# STlink_V3E_PWR.net
KiCad netlist of a schematic drawn in Altium Designer
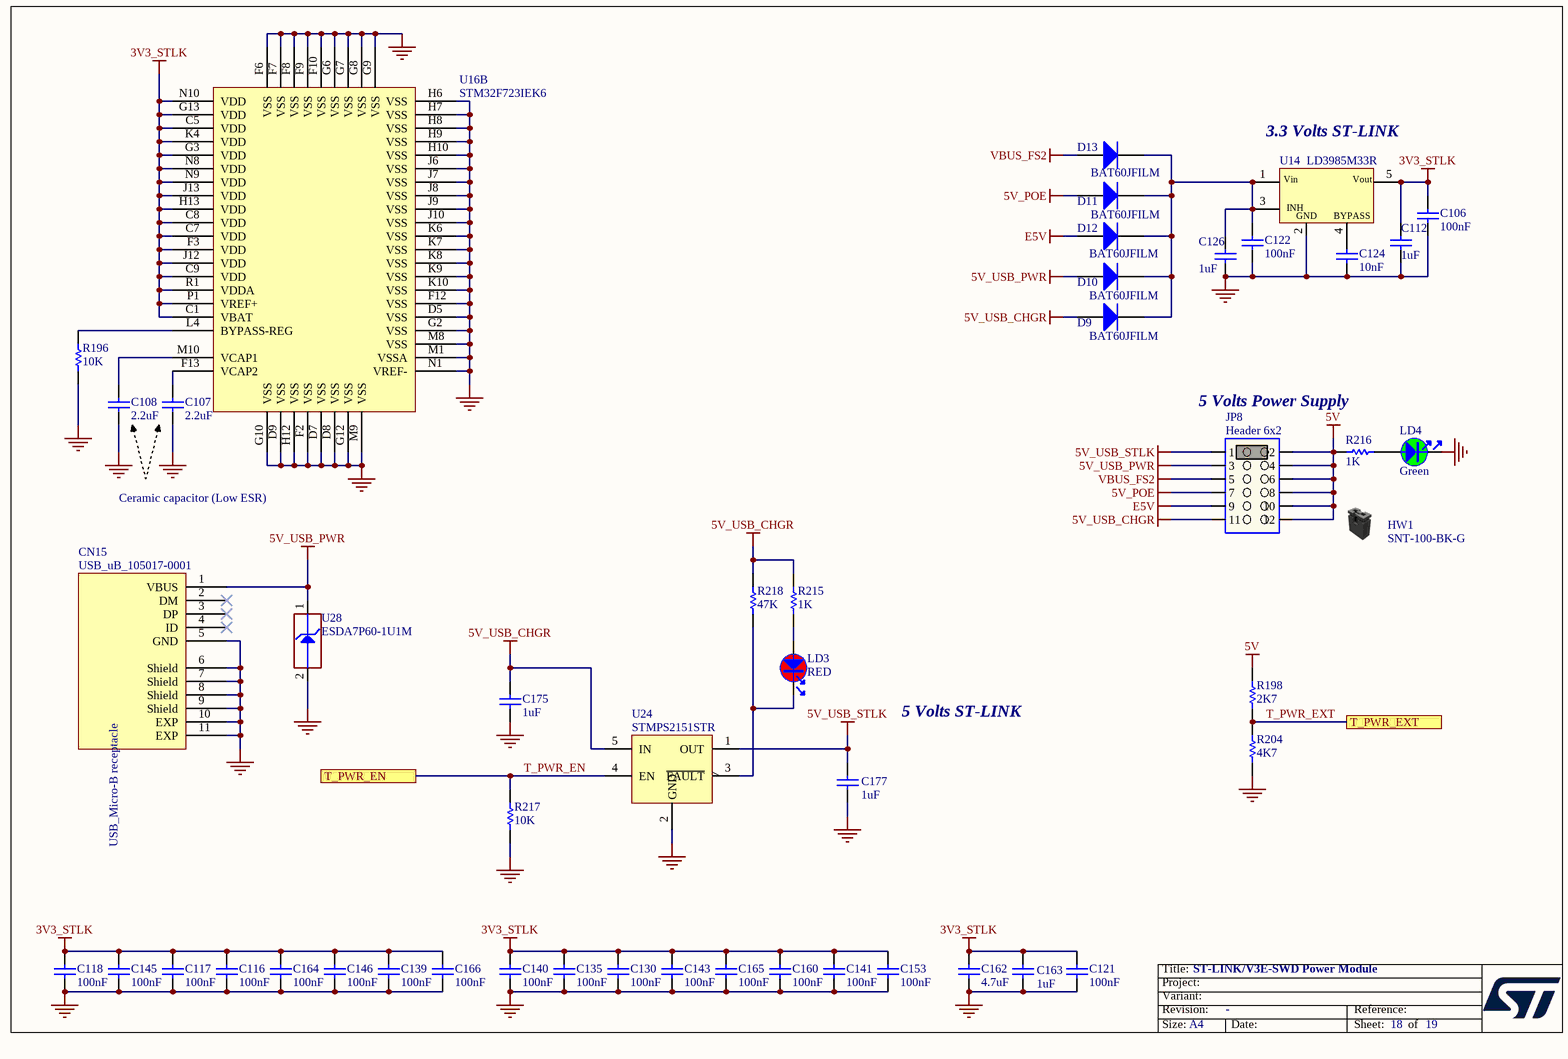
[diagram p0: STlink_V3E_PWR.SchDoc]

(export (version "E")
  (design (tool "Eeschema 10.0.6"))
  (components
    (comp (ref "C106")
      (value "100nF")
      (footprint "C0402")
      (description "Capacitor, MLCC, 100nF, 16V, X7R, +/-10%, 0402, T=0.5mm")
      (fields
        (field (name "INTERNAL_PART_NUMBER") "MCD-00006")
        (field (name "MANUFACTURER_PART_NUMBER") "CC0402KRX7R7BB104")
      )
      (libsource (lib "MCD_PARTS_database") (part "Capacitor"))
    )
    (comp (ref "C107")
      (value "2.2uF")
      (footprint "C1206_H1P15")
      (description "Capacitor, MLCC, 2.2uF, 16V, X7R, 10%, 1206, T=1,15mm")
      (fields
        (field (name "INTERNAL_PART_NUMBER") "MCD-00008")
        (field (name "MANUFACTURER_PART_NUMBER") "CC1206KKX7R7BB225")
        (field (name "PROVIDED_BY") "Subcon")
      )
      (libsource (lib "MCD_PARTS_database") (part "Capacitor"))
    )
    (comp (ref "C108")
      (value "2.2uF")
      (footprint "C1206_H1P15")
      (description "Capacitor, MLCC, 2.2uF, 16V, X7R, 10%, 1206, T=1,15mm")
      (fields
        (field (name "INTERNAL_PART_NUMBER") "MCD-00008")
        (field (name "MANUFACTURER_PART_NUMBER") "CC1206KKX7R7BB225")
        (field (name "PROVIDED_BY") "Subcon")
      )
      (libsource (lib "MCD_PARTS_database") (part "Capacitor"))
    )
    (comp (ref "C112")
      (value "1uF")
      (footprint "C0603")
      (description "Capacitor, MLCC, 1uF, 16V, X5R, 10%, 0603, T=0,8mm")
      (fields
        (field (name "INTERNAL_PART_NUMBER") "MCD-00010")
        (field (name "MANUFACTURER_PART_NUMBER") "CC0603KRX5R7BB105")
        (field (name "PROVIDED_BY") "Subcon")
      )
      (libsource (lib "MCD_PARTS_database") (part "Capacitor"))
    )
    (comp (ref "C116")
      (value "100nF")
      (footprint "C0402")
      (description "Capacitor, MLCC, 100nF, 16V, X7R, +/-10%, 0402, T=0.5mm")
      (fields
        (field (name "INTERNAL_PART_NUMBER") "MCD-00006")
        (field (name "MANUFACTURER_PART_NUMBER") "CC0402KRX7R7BB104")
      )
      (libsource (lib "MCD_PARTS_database") (part "Capacitor"))
    )
    (comp (ref "C117")
      (value "100nF")
      (footprint "C0402")
      (description "Capacitor, MLCC, 100nF, 16V, X7R, +/-10%, 0402, T=0.5mm")
      (fields
        (field (name "INTERNAL_PART_NUMBER") "MCD-00006")
        (field (name "MANUFACTURER_PART_NUMBER") "CC0402KRX7R7BB104")
      )
      (libsource (lib "MCD_PARTS_database") (part "Capacitor"))
    )
    (comp (ref "C118")
      (value "100nF")
      (footprint "C0402")
      (description "Capacitor, MLCC, 100nF, 16V, X7R, +/-10%, 0402, T=0.5mm")
      (fields
        (field (name "INTERNAL_PART_NUMBER") "MCD-00006")
        (field (name "MANUFACTURER_PART_NUMBER") "CC0402KRX7R7BB104")
      )
      (libsource (lib "MCD_PARTS_database") (part "Capacitor"))
    )
    (comp (ref "C121")
      (value "100nF")
      (footprint "C0402")
      (description "Capacitor, MLCC, 100nF, 16V, X7R, +/-10%, 0402, T=0.5mm")
      (fields
        (field (name "INTERNAL_PART_NUMBER") "MCD-00006")
        (field (name "MANUFACTURER_PART_NUMBER") "CC0402KRX7R7BB104")
      )
      (libsource (lib "MCD_PARTS_database") (part "Capacitor"))
    )
    (comp (ref "C122")
      (value "100nF")
      (footprint "C0402")
      (description "Capacitor, MLCC, 100nF, 16V, X7R, +/-10%, 0402, T=0.5mm")
      (fields
        (field (name "INTERNAL_PART_NUMBER") "MCD-00006")
        (field (name "MANUFACTURER_PART_NUMBER") "CC0402KRX7R7BB104")
      )
      (libsource (lib "MCD_PARTS_database") (part "Capacitor"))
    )
    (comp (ref "C124")
      (value "10nF")
      (footprint "C0402")
      (description "Capacitor, MLCC, 10nF, 16V, X7R, 10%, 0402, T=0.5mm")
      (fields
        (field (name "INTERNAL_PART_NUMBER") "MCD-00011")
        (field (name "MANUFACTURER_PART_NUMBER") "CC0402KRX7R7BB103")
        (field (name "PROVIDED_BY") "Subcon")
      )
      (libsource (lib "MCD_PARTS_database") (part "Capacitor"))
    )
    (comp (ref "C126")
      (value "1uF")
      (footprint "C0603")
      (description "Capacitor, MLCC, 1uF, 6V3, X5R, 10%, 0603, T=0,8mm")
      (fields
        (field (name "INTERNAL_PART_NUMBER") "MCD-00238")
        (field (name "MANUFACTURER_PART_NUMBER") "CC0603KRX5R5BB105")
        (field (name "PROVIDED_BY") "Subcon")
      )
      (libsource (lib "MCD_PARTS_database") (part "Capacitor"))
    )
    (comp (ref "C130")
      (value "100nF")
      (footprint "C0402")
      (description "Capacitor, MLCC, 100nF, 16V, X7R, +/-10%, 0402, T=0.5mm")
      (fields
        (field (name "INTERNAL_PART_NUMBER") "MCD-00006")
        (field (name "MANUFACTURER_PART_NUMBER") "CC0402KRX7R7BB104")
      )
      (libsource (lib "MCD_PARTS_database") (part "Capacitor"))
    )
    (comp (ref "C135")
      (value "100nF")
      (footprint "C0402")
      (description "Capacitor, MLCC, 100nF, 16V, X7R, +/-10%, 0402, T=0.5mm")
      (fields
        (field (name "INTERNAL_PART_NUMBER") "MCD-00006")
        (field (name "MANUFACTURER_PART_NUMBER") "CC0402KRX7R7BB104")
      )
      (libsource (lib "MCD_PARTS_database") (part "Capacitor"))
    )
    (comp (ref "C139")
      (value "100nF")
      (footprint "C0402")
      (description "Capacitor, MLCC, 100nF, 16V, X7R, +/-10%, 0402, T=0.5mm")
      (fields
        (field (name "INTERNAL_PART_NUMBER") "MCD-00006")
        (field (name "MANUFACTURER_PART_NUMBER") "CC0402KRX7R7BB104")
      )
      (libsource (lib "MCD_PARTS_database") (part "Capacitor"))
    )
    (comp (ref "C140")
      (value "100nF")
      (footprint "C0402")
      (description "Capacitor, MLCC, 100nF, 16V, X7R, +/-10%, 0402, T=0.5mm")
      (fields
        (field (name "INTERNAL_PART_NUMBER") "MCD-00006")
        (field (name "MANUFACTURER_PART_NUMBER") "CC0402KRX7R7BB104")
      )
      (libsource (lib "MCD_PARTS_database") (part "Capacitor"))
    )
    (comp (ref "C141")
      (value "100nF")
      (footprint "C0402")
      (description "Capacitor, MLCC, 100nF, 16V, X7R, +/-10%, 0402, T=0.5mm")
      (fields
        (field (name "INTERNAL_PART_NUMBER") "MCD-00006")
        (field (name "MANUFACTURER_PART_NUMBER") "CC0402KRX7R7BB104")
      )
      (libsource (lib "MCD_PARTS_database") (part "Capacitor"))
    )
    (comp (ref "C143")
      (value "100nF")
      (footprint "C0402")
      (description "Capacitor, MLCC, 100nF, 16V, X7R, +/-10%, 0402, T=0.5mm")
      (fields
        (field (name "INTERNAL_PART_NUMBER") "MCD-00006")
        (field (name "MANUFACTURER_PART_NUMBER") "CC0402KRX7R7BB104")
      )
      (libsource (lib "MCD_PARTS_database") (part "Capacitor"))
    )
    (comp (ref "C145")
      (value "100nF")
      (footprint "C0402")
      (description "Capacitor, MLCC, 100nF, 16V, X7R, +/-10%, 0402, T=0.5mm")
      (fields
        (field (name "INTERNAL_PART_NUMBER") "MCD-00006")
        (field (name "MANUFACTURER_PART_NUMBER") "CC0402KRX7R7BB104")
      )
      (libsource (lib "MCD_PARTS_database") (part "Capacitor"))
    )
    (comp (ref "C146")
      (value "100nF")
      (footprint "C0402")
      (description "Capacitor, MLCC, 100nF, 16V, X7R, +/-10%, 0402, T=0.5mm")
      (fields
        (field (name "INTERNAL_PART_NUMBER") "MCD-00006")
        (field (name "MANUFACTURER_PART_NUMBER") "CC0402KRX7R7BB104")
      )
      (libsource (lib "MCD_PARTS_database") (part "Capacitor"))
    )
    (comp (ref "C153")
      (value "100nF")
      (footprint "C0402")
      (description "Capacitor, MLCC, 100nF, 16V, X7R, +/-10%, 0402, T=0.5mm")
      (fields
        (field (name "INTERNAL_PART_NUMBER") "MCD-00006")
        (field (name "MANUFACTURER_PART_NUMBER") "CC0402KRX7R7BB104")
      )
      (libsource (lib "MCD_PARTS_database") (part "Capacitor"))
    )
    (comp (ref "C160")
      (value "100nF")
      (footprint "C0402")
      (description "Capacitor, MLCC, 100nF, 16V, X7R, +/-10%, 0402, T=0.5mm")
      (fields
        (field (name "INTERNAL_PART_NUMBER") "MCD-00006")
        (field (name "MANUFACTURER_PART_NUMBER") "CC0402KRX7R7BB104")
      )
      (libsource (lib "MCD_PARTS_database") (part "Capacitor"))
    )
    (comp (ref "C162")
      (value "4.7uF")
      (footprint "C0603")
      (description "Capacitor, MLCC, 4.7uF, 16V, X5R, 10%, 0603, T=0.8mm")
      (fields
        (field (name "INTERNAL_PART_NUMBER") "MCD-00009")
        (field (name "MANUFACTURER_PART_NUMBER") "CC0603KRX5R7BB475")
        (field (name "PROVIDED_BY") "subcon")
      )
      (libsource (lib "MCD_PARTS_database") (part "Capacitor"))
    )
    (comp (ref "C163")
      (value "1uF")
      (footprint "C0603")
      (description "Capacitor, MLCC, 1uF, 16V, X5R, 10%, 0603, T=0,8mm")
      (fields
        (field (name "INTERNAL_PART_NUMBER") "MCD-00010")
        (field (name "MANUFACTURER_PART_NUMBER") "CC0603KRX5R7BB105")
        (field (name "PROVIDED_BY") "Subcon")
      )
      (libsource (lib "MCD_PARTS_database") (part "Capacitor"))
    )
    (comp (ref "C164")
      (value "100nF")
      (footprint "C0402")
      (description "Capacitor, MLCC, 100nF, 16V, X7R, +/-10%, 0402, T=0.5mm")
      (fields
        (field (name "INTERNAL_PART_NUMBER") "MCD-00006")
        (field (name "MANUFACTURER_PART_NUMBER") "CC0402KRX7R7BB104")
      )
      (libsource (lib "MCD_PARTS_database") (part "Capacitor"))
    )
    (comp (ref "C165")
      (value "100nF")
      (footprint "C0402")
      (description "Capacitor, MLCC, 100nF, 16V, X7R, +/-10%, 0402, T=0.5mm")
      (fields
        (field (name "INTERNAL_PART_NUMBER") "MCD-00006")
        (field (name "MANUFACTURER_PART_NUMBER") "CC0402KRX7R7BB104")
      )
      (libsource (lib "MCD_PARTS_database") (part "Capacitor"))
    )
    (comp (ref "C166")
      (value "100nF")
      (footprint "C0402")
      (description "Capacitor, MLCC, 100nF, 16V, X7R, +/-10%, 0402, T=0.5mm")
      (fields
        (field (name "INTERNAL_PART_NUMBER") "MCD-00006")
        (field (name "MANUFACTURER_PART_NUMBER") "CC0402KRX7R7BB104")
      )
      (libsource (lib "MCD_PARTS_database") (part "Capacitor"))
    )
    (comp (ref "C175")
      (value "1uF")
      (footprint "C0603")
      (description "Capacitor, MLCC, 1uF, 16V, X5R, 10%, 0603, T=0,8mm")
      (fields
        (field (name "INTERNAL_PART_NUMBER") "MCD-00010")
        (field (name "MANUFACTURER_PART_NUMBER") "CC0603KRX5R7BB105")
        (field (name "PROVIDED_BY") "Subcon")
      )
      (libsource (lib "MCD_PARTS_database") (part "Capacitor"))
    )
    (comp (ref "C177")
      (value "1uF")
      (footprint "C0603")
      (description "Capacitor, MLCC, 1uF, 16V, X5R, 10%, 0603, T=0,8mm")
      (fields
        (field (name "INTERNAL_PART_NUMBER") "MCD-00010")
        (field (name "MANUFACTURER_PART_NUMBER") "CC0603KRX5R7BB105")
        (field (name "PROVIDED_BY") "Subcon")
      )
      (libsource (lib "MCD_PARTS_database") (part "Capacitor"))
    )
    (comp (ref "CN15")
      (value "USB_uB_105017-0001")
      (footprint "CON_USBMICROB_MOLEX_105017-0001_H2P90")
      (description "USB-MICRO-B, 0.65mm, RA, SMT, Bottom Mount,")
      (fields
        (field (name "INTERNAL_PART_NUMBER") "MCD-00028")
        (field (name "MANUFACTURER_PART_NUMBER") "1050170001")
        (field (name "PROVIDED_BY") "Subcon")
      )
      (libsource (lib "MCD_PARTS_database") (part "USB_uB_105017.0001"))
    )
    (comp (ref "D9")
      (value "BAT60JFILM")
      (footprint "DIO_SOD323")
      (fields
        (field (name "INTERNAL_PART_NUMBER") "MCD-00034")
        (field (name "MANUFACTURER") "STMICROELECTRONICS")
        (field (name "BMS_PART_NUMBER") "9151097")
        (field (name "PROVIDED_BY") "Subcon")
      )
      (libsource (lib "MCD_PARTS_database") (part "BAT60JFILM"))
    )
    (comp (ref "D10")
      (value "BAT60JFILM")
      (footprint "DIO_SOD323")
      (fields
        (field (name "INTERNAL_PART_NUMBER") "MCD-00034")
        (field (name "MANUFACTURER") "STMICROELECTRONICS")
        (field (name "BMS_PART_NUMBER") "9151097")
        (field (name "PROVIDED_BY") "Subcon")
      )
      (libsource (lib "MCD_PARTS_database") (part "BAT60JFILM"))
    )
    (comp (ref "D11")
      (value "BAT60JFILM")
      (footprint "DIO_SOD323")
      (fields
        (field (name "INTERNAL_PART_NUMBER") "MCD-00034")
        (field (name "MANUFACTURER") "STMICROELECTRONICS")
        (field (name "BMS_PART_NUMBER") "9151097")
        (field (name "PROVIDED_BY") "Subcon")
      )
      (libsource (lib "MCD_PARTS_database") (part "BAT60JFILM"))
    )
    (comp (ref "D12")
      (value "BAT60JFILM")
      (footprint "DIO_SOD323")
      (fields
        (field (name "INTERNAL_PART_NUMBER") "MCD-00034")
        (field (name "MANUFACTURER") "STMICROELECTRONICS")
        (field (name "BMS_PART_NUMBER") "9151097")
        (field (name "PROVIDED_BY") "Subcon")
      )
      (libsource (lib "MCD_PARTS_database") (part "BAT60JFILM"))
    )
    (comp (ref "D13")
      (value "BAT60JFILM")
      (footprint "DIO_SOD323")
      (fields
        (field (name "INTERNAL_PART_NUMBER") "MCD-00034")
        (field (name "MANUFACTURER") "STMICROELECTRONICS")
        (field (name "BMS_PART_NUMBER") "9151097")
        (field (name "PROVIDED_BY") "Subcon")
      )
      (libsource (lib "MCD_PARTS_database") (part "BAT60JFILM"))
    )
    (comp (ref "HW1")
      (value "SNT-100-BK-G")
      (description "Shunt, 2.54mm, Black, 4.3A, 6.1mm, 5mR")
      (fields (field (name "INTERNAL_PART_NUMBER") "MCD-00043") (field (name "MANUFACTURER") "SAMTEC"))
      (libsource (lib "MCD_PARTS_database") (part "Shunt Black 2.54mm"))
    )
    (comp (ref "JP8")
      (value "Header 6x2")
      (footprint "CON_SAMTEC_TSW-106-07-X-D")
      (description "Header, 6x2, 2.54mm, VR, TH, T=5.84mm/2.54mm")
      (fields
        (field (name "INTERNAL_PART_NUMBER") "MCD-00691")
        (field (name "MANUFACTURER_PART_NUMBER") "TSW-106-07-G-D")
      )
      (libsource (lib "MCD_PARTS_database") (part "Jumper_Header 6x2 Fitted 1-2"))
    )
    (comp (ref "LD3")
      (value "RED")
      (footprint "LED_0603_RED")
      (description "LED, Red, VF : Min=1.75V , Max=2.35V, 25mA, 0603")
      (fields (field (name "INTERNAL_PART_NUMBER") "MCD-02899") (field (name "MANUFACTURER") "EVERLIGHT"))
      (libsource (lib "MCD_PARTS_database") (part "LED_red"))
    )
    (comp (ref "LD4")
      (value "Green")
      (footprint "LED_0603_GREEN")
      (description "LED, Green, 2V, 20mA, 0603")
      (fields (field (name "INTERNAL_PART_NUMBER") "MCD-02900") (field (name "MANUFACTURER") "EVERLIGHT"))
      (libsource (lib "MCD_PARTS_database") (part "LED_green"))
    )
    (comp (ref "R196")
      (value "10K")
      (footprint "R0402")
      (description "Resistor,10K,0402,1%,1/16W")
      (fields
        (field (name "INTERNAL_PART_NUMBER") "MCD-00053")
        (field (name "MANUFACTURER_PART_NUMBER") "RC0402FR-0710KL")
        (field (name "PROVIDED_BY") "subcon")
      )
      (libsource (lib "MCD_PARTS_database") (part "Resistor"))
    )
    (comp (ref "R198")
      (value "2K7")
      (footprint "R0402")
      (description "Resistor,2K7,0402,1%,1/16W")
      (fields
        (field (name "INTERNAL_PART_NUMBER") "MCD-00055")
        (field (name "MANUFACTURER_PART_NUMBER") "RC0402FR-072K7L")
        (field (name "PROVIDED_BY") "Subcon")
      )
      (libsource (lib "MCD_PARTS_database") (part "Resistor"))
    )
    (comp (ref "R204")
      (value "4K7")
      (footprint "R0402")
      (description "Resistor,4K7,0402,1%,1/16W")
      (fields
        (field (name "INTERNAL_PART_NUMBER") "MCD-00065")
        (field (name "MANUFACTURER_PART_NUMBER") "RC0402FR-074K7L")
        (field (name "PROVIDED_BY") "Subcon")
      )
      (libsource (lib "MCD_PARTS_database") (part "Resistor"))
    )
    (comp (ref "R215")
      (value "1K")
      (footprint "R0402")
      (description "Resistor,1K,0402,1%,1/16W")
      (fields
        (field (name "INTERNAL_PART_NUMBER") "MCD-00061")
        (field (name "MANUFACTURER_PART_NUMBER") "RC0402FR-071KL")
        (field (name "PROVIDED_BY") "Subcon")
      )
      (libsource (lib "MCD_PARTS_database") (part "Resistor"))
    )
    (comp (ref "R216")
      (value "1K")
      (footprint "R0603")
      (description "Resistor,1K,0603,1%,1/10W")
      (fields
        (field (name "INTERNAL_PART_NUMBER") "MCD-00070")
        (field (name "MANUFACTURER_PART_NUMBER") "RC0603FR-071KL")
        (field (name "PROVIDED_BY") "Subcon")
      )
      (libsource (lib "MCD_PARTS_database") (part "Resistor"))
    )
    (comp (ref "R217")
      (value "10K")
      (footprint "R0402")
      (description "Resistor,10K,0402,1%,1/16W")
      (fields
        (field (name "INTERNAL_PART_NUMBER") "MCD-00053")
        (field (name "MANUFACTURER_PART_NUMBER") "RC0402FR-0710KL")
        (field (name "PROVIDED_BY") "subcon")
      )
      (libsource (lib "MCD_PARTS_database") (part "Resistor"))
    )
    (comp (ref "R218")
      (value "47K")
      (footprint "R0402")
      (description "Resistor,47K,0402,1%,1/16W")
      (fields
        (field (name "INTERNAL_PART_NUMBER") "MCD-00063")
        (field (name "MANUFACTURER_PART_NUMBER") "RC0402FR-0747KL")
        (field (name "PROVIDED_BY") "Subcon")
      )
      (libsource (lib "MCD_PARTS_database") (part "Resistor"))
    )
    (comp (ref "U14")
      (value "LD3985M33R")
      (footprint "REG_SOT23-5L")
      (description "Ultra low drop-low noise BiCMOS voltage, regulators low ESR capacitors compatible")
      (fields
        (field (name "INTERNAL_PART_NUMBER") "MCD-00086")
        (field (name "MANUFACTURER") "STMICROELECTRONICS")
        (field (name "PROVIDED_BY") "Subcon")
      )
      (libsource (lib "MCD_PARTS_database") (part "LD3985M33R"))
    )
    (comp (ref "U16")
      (value "STM32F723IEK6")
      (footprint "ICC_UFBGA201_176+25_10X10_P065")
      (description "STM32F723IEK  (STM32F7) BGA176")
      (fields
        (field (name "INTERNAL_PART_NUMBER") "MCD-00596")
        (field (name "MANUFACTURER") "STMICROELECTRONICS")
        (field (name "PROVIDED_BY") "SUBCO with ST control")
      )
      (libsource (lib "MCD_PARTS_database") (part "ST-LINKV3E_SWD"))
    )
    (comp (ref "U24")
      (value "STMPS2151STR")
      (footprint "MOS_SOT23-5L")
      (description "500mA, Enhanced single channel power switches with active high enable pin")
      (fields
        (field (name "INTERNAL_PART_NUMBER") "MCD-00159")
        (field (name "MANUFACTURER") "STMICROELECTRONICS")
        (field (name "PROVIDED_BY") "Subcon")
      )
      (libsource (lib "MCD_PARTS_database") (part "STMPS2151STR"))
    )
    (comp (ref "U28")
      (value "ESDA7P60-1U1M")
      (footprint "ESD_QFN2_1P6X1_P125")
      (description "High power transient voltage suppressor, 7V breakdown")
      (fields
        (field (name "INTERNAL_PART_NUMBER") "MCD-00251")
        (field (name "MANUFACTURER") "STMICROELECTRONICS")
        (field (name "PROVIDED_BY") "Subcon")
      )
      (libsource (lib "MCD_PARTS_database") (part "ESDA7P60-1U1M"))
    )
  )
  (nets
    (net (code "1") (name "/T_PWR_EN") (class "Default")
      (node (ref "R217") (pin "1") (pinfunction "1_1") (pintype "passive"))
      (node (ref "U24") (pin "4") (pinfunction "EN_4") (pintype "passive"))
    )
    (net (code "2") (name "/T_PWR_EXT") (class "Default")
      (node (ref "R198") (pin "1") (pinfunction "1_1") (pintype "passive"))
      (node (ref "R204") (pin "2") (pinfunction "2_2") (pintype "passive"))
    )
    (net (code "3") (name "3V3_STLK") (class "Default")
      (node (ref "C106") (pin "2") (pinfunction "2_2") (pintype "passive"))
      (node (ref "C112") (pin "2") (pinfunction "2_2") (pintype "passive"))
      (node (ref "C116") (pin "2") (pinfunction "2_2") (pintype "passive"))
      (node (ref "C117") (pin "2") (pinfunction "2_2") (pintype "passive"))
      (node (ref "C118") (pin "2") (pinfunction "2_2") (pintype "passive"))
      (node (ref "C121") (pin "2") (pinfunction "2_2") (pintype "passive"))
      (node (ref "C130") (pin "2") (pinfunction "2_2") (pintype "passive"))
      (node (ref "C135") (pin "2") (pinfunction "2_2") (pintype "passive"))
      (node (ref "C139") (pin "2") (pinfunction "2_2") (pintype "passive"))
      (node (ref "C140") (pin "2") (pinfunction "2_2") (pintype "passive"))
      (node (ref "C141") (pin "2") (pinfunction "2_2") (pintype "passive"))
      (node (ref "C143") (pin "2") (pinfunction "2_2") (pintype "passive"))
      (node (ref "C145") (pin "2") (pinfunction "2_2") (pintype "passive"))
      (node (ref "C146") (pin "2") (pinfunction "2_2") (pintype "passive"))
      (node (ref "C153") (pin "2") (pinfunction "2_2") (pintype "passive"))
      (node (ref "C160") (pin "2") (pinfunction "2_2") (pintype "passive"))
      (node (ref "C162") (pin "2") (pinfunction "2_2") (pintype "passive"))
      (node (ref "C163") (pin "2") (pinfunction "2_2") (pintype "passive"))
      (node (ref "C164") (pin "2") (pinfunction "2_2") (pintype "passive"))
      (node (ref "C165") (pin "2") (pinfunction "2_2") (pintype "passive"))
      (node (ref "C166") (pin "2") (pinfunction "2_2") (pintype "passive"))
      (node (ref "U14") (pin "5") (pinfunction "Vout_5") (pintype "passive"))
      (node (ref "U16") (pin "C1") (pinfunction "VBAT_C1") (pintype "passive"))
      (node (ref "U16") (pin "C5") (pinfunction "VDD_C5") (pintype "passive"))
      (node (ref "U16") (pin "C7") (pinfunction "VDD_C7") (pintype "passive"))
      (node (ref "U16") (pin "C8") (pinfunction "VDD_C8") (pintype "passive"))
      (node (ref "U16") (pin "C9") (pinfunction "VDD_C9") (pintype "passive"))
      (node (ref "U16") (pin "F3") (pinfunction "VDD_F3") (pintype "passive"))
      (node (ref "U16") (pin "G13") (pinfunction "VDD_G13") (pintype "passive"))
      (node (ref "U16") (pin "G3") (pinfunction "VDD_G3") (pintype "passive"))
      (node (ref "U16") (pin "H13") (pinfunction "VDD_H13") (pintype "passive"))
      (node (ref "U16") (pin "J12") (pinfunction "VDD_J12") (pintype "passive"))
      (node (ref "U16") (pin "J13") (pinfunction "VDD_J13") (pintype "passive"))
      (node (ref "U16") (pin "K4") (pinfunction "VDD_K4") (pintype "passive"))
      (node (ref "U16") (pin "N10") (pinfunction "VDD_N10") (pintype "passive"))
      (node (ref "U16") (pin "N8") (pinfunction "VDD_N8") (pintype "passive"))
      (node (ref "U16") (pin "N9") (pinfunction "VDD_N9") (pintype "passive"))
      (node (ref "U16") (pin "P1") (pinfunction "VREF+_P1") (pintype "passive"))
      (node (ref "U16") (pin "R1") (pinfunction "VDDA_R1") (pintype "passive"))
    )
    (net (code "4") (name "5V") (class "Default")
      (node (ref "JP8") (pin "10") (pinfunction "10_10") (pintype "passive"))
      (node (ref "JP8") (pin "12") (pinfunction "12_12") (pintype "passive"))
      (node (ref "JP8") (pin "2") (pinfunction "2_2") (pintype "passive"))
      (node (ref "JP8") (pin "4") (pinfunction "4_4") (pintype "passive"))
      (node (ref "JP8") (pin "6") (pinfunction "6_6") (pintype "passive"))
      (node (ref "JP8") (pin "8") (pinfunction "8_8") (pintype "passive"))
      (node (ref "R198") (pin "2") (pinfunction "2_2") (pintype "passive"))
      (node (ref "R216") (pin "1") (pinfunction "1_1") (pintype "passive"))
    )
    (net (code "5") (name "5V_POE") (class "Default")
      (node (ref "D11") (pin "1") (pinfunction "A_1") (pintype "passive"))
      (node (ref "JP8") (pin "7") (pinfunction "7_7") (pintype "passive"))
    )
    (net (code "6") (name "5V_USB_CHGR") (class "Default")
      (node (ref "C175") (pin "2") (pinfunction "2_2") (pintype "passive"))
      (node (ref "D9") (pin "1") (pinfunction "A_1") (pintype "passive"))
      (node (ref "JP8") (pin "11") (pinfunction "11_11") (pintype "passive"))
      (node (ref "R215") (pin "2") (pinfunction "2_2") (pintype "passive"))
      (node (ref "R218") (pin "2") (pinfunction "2_2") (pintype "passive"))
      (node (ref "U24") (pin "5") (pinfunction "IN_5") (pintype "passive"))
    )
    (net (code "7") (name "5V_USB_PWR") (class "Default")
      (node (ref "CN15") (pin "1") (pinfunction "VBUS_1") (pintype "passive"))
      (node (ref "D10") (pin "1") (pinfunction "A_1") (pintype "passive"))
      (node (ref "JP8") (pin "3") (pinfunction "3_3") (pintype "passive"))
      (node (ref "U28") (pin "1") (pinfunction "IO1_1") (pintype "passive"))
    )
    (net (code "8") (name "5V_USB_STLK") (class "Default")
      (node (ref "C177") (pin "2") (pinfunction "2_2") (pintype "passive"))
      (node (ref "JP8") (pin "1") (pinfunction "1_1") (pintype "passive"))
      (node (ref "U24") (pin "1") (pinfunction "OUT_1") (pintype "passive"))
    )
    (net (code "9") (name "E5V") (class "Default")
      (node (ref "D12") (pin "1") (pinfunction "A_1") (pintype "passive"))
      (node (ref "JP8") (pin "9") (pinfunction "9_9") (pintype "passive"))
    )
    (net (code "10") (name "GND") (class "Default")
      (node (ref "C106") (pin "1") (pinfunction "1_1") (pintype "passive"))
      (node (ref "C107") (pin "1") (pinfunction "1_1") (pintype "passive"))
      (node (ref "C108") (pin "1") (pinfunction "1_1") (pintype "passive"))
      (node (ref "C112") (pin "1") (pinfunction "1_1") (pintype "passive"))
      (node (ref "C116") (pin "1") (pinfunction "1_1") (pintype "passive"))
      (node (ref "C117") (pin "1") (pinfunction "1_1") (pintype "passive"))
      (node (ref "C118") (pin "1") (pinfunction "1_1") (pintype "passive"))
      (node (ref "C121") (pin "1") (pinfunction "1_1") (pintype "passive"))
      (node (ref "C122") (pin "1") (pinfunction "1_1") (pintype "passive"))
      (node (ref "C124") (pin "1") (pinfunction "1_1") (pintype "passive"))
      (node (ref "C126") (pin "2") (pinfunction "2_2") (pintype "passive"))
      (node (ref "C130") (pin "1") (pinfunction "1_1") (pintype "passive"))
      (node (ref "C135") (pin "1") (pinfunction "1_1") (pintype "passive"))
      (node (ref "C139") (pin "1") (pinfunction "1_1") (pintype "passive"))
      (node (ref "C140") (pin "1") (pinfunction "1_1") (pintype "passive"))
      (node (ref "C141") (pin "1") (pinfunction "1_1") (pintype "passive"))
      (node (ref "C143") (pin "1") (pinfunction "1_1") (pintype "passive"))
      (node (ref "C145") (pin "1") (pinfunction "1_1") (pintype "passive"))
      (node (ref "C146") (pin "1") (pinfunction "1_1") (pintype "passive"))
      (node (ref "C153") (pin "1") (pinfunction "1_1") (pintype "passive"))
      (node (ref "C160") (pin "1") (pinfunction "1_1") (pintype "passive"))
      (node (ref "C162") (pin "1") (pinfunction "1_1") (pintype "passive"))
      (node (ref "C163") (pin "1") (pinfunction "1_1") (pintype "passive"))
      (node (ref "C164") (pin "1") (pinfunction "1_1") (pintype "passive"))
      (node (ref "C165") (pin "1") (pinfunction "1_1") (pintype "passive"))
      (node (ref "C166") (pin "1") (pinfunction "1_1") (pintype "passive"))
      (node (ref "C175") (pin "1") (pinfunction "1_1") (pintype "passive"))
      (node (ref "C177") (pin "1") (pinfunction "1_1") (pintype "passive"))
      (node (ref "CN15") (pin "10") (pinfunction "EXP_10") (pintype "passive"))
      (node (ref "CN15") (pin "11") (pinfunction "EXP_11") (pintype "passive"))
      (node (ref "CN15") (pin "5") (pinfunction "GND_5") (pintype "passive"))
      (node (ref "CN15") (pin "6") (pinfunction "Shield_6") (pintype "passive"))
      (node (ref "CN15") (pin "7") (pinfunction "Shield_7") (pintype "passive"))
      (node (ref "CN15") (pin "8") (pinfunction "Shield_8") (pintype "passive"))
      (node (ref "CN15") (pin "9") (pinfunction "Shield_9") (pintype "passive"))
      (node (ref "LD4") (pin "2") (pintype "passive"))
      (node (ref "R196") (pin "1") (pinfunction "1_1") (pintype "passive"))
      (node (ref "R204") (pin "1") (pinfunction "1_1") (pintype "passive"))
      (node (ref "R217") (pin "2") (pinfunction "2_2") (pintype "passive"))
      (node (ref "U14") (pin "2") (pinfunction "GND_2") (pintype "passive"))
      (node (ref "U16") (pin "D5") (pinfunction "VSS_D5") (pintype "passive"))
      (node (ref "U16") (pin "D7") (pinfunction "VSS_D7") (pintype "passive"))
      (node (ref "U16") (pin "D8") (pinfunction "VSS_D8") (pintype "passive"))
      (node (ref "U16") (pin "D9") (pinfunction "VSS_D9") (pintype "passive"))
      (node (ref "U16") (pin "F10") (pinfunction "VSS_F10") (pintype "passive"))
      (node (ref "U16") (pin "F12") (pinfunction "VSS_F12") (pintype "passive"))
      (node (ref "U16") (pin "F2") (pinfunction "VSS_F2") (pintype "passive"))
      (node (ref "U16") (pin "F6") (pinfunction "VSS_F6") (pintype "passive"))
      (node (ref "U16") (pin "F7") (pinfunction "VSS_F7") (pintype "passive"))
      (node (ref "U16") (pin "F8") (pinfunction "VSS_F8") (pintype "passive"))
      (node (ref "U16") (pin "F9") (pinfunction "VSS_F9") (pintype "passive"))
      (node (ref "U16") (pin "G10") (pinfunction "VSS_G10") (pintype "passive"))
      (node (ref "U16") (pin "G12") (pinfunction "VSS_G12") (pintype "passive"))
      (node (ref "U16") (pin "G2") (pinfunction "VSS_G2") (pintype "passive"))
      (node (ref "U16") (pin "G6") (pinfunction "VSS_G6") (pintype "passive"))
      (node (ref "U16") (pin "G7") (pinfunction "VSS_G7") (pintype "passive"))
      (node (ref "U16") (pin "G8") (pinfunction "VSS_G8") (pintype "passive"))
      (node (ref "U16") (pin "G9") (pinfunction "VSS_G9") (pintype "passive"))
      (node (ref "U16") (pin "H10") (pinfunction "VSS_H10") (pintype "passive"))
      (node (ref "U16") (pin "H12") (pinfunction "VSS_H12") (pintype "passive"))
      (node (ref "U16") (pin "H6") (pinfunction "VSS_H6") (pintype "passive"))
      (node (ref "U16") (pin "H7") (pinfunction "VSS_H7") (pintype "passive"))
      (node (ref "U16") (pin "H8") (pinfunction "VSS_H8") (pintype "passive"))
      (node (ref "U16") (pin "H9") (pinfunction "VSS_H9") (pintype "passive"))
      (node (ref "U16") (pin "J10") (pinfunction "VSS_J10") (pintype "passive"))
      (node (ref "U16") (pin "J6") (pinfunction "VSS_J6") (pintype "passive"))
      (node (ref "U16") (pin "J7") (pinfunction "VSS_J7") (pintype "passive"))
      (node (ref "U16") (pin "J8") (pinfunction "VSS_J8") (pintype "passive"))
      (node (ref "U16") (pin "J9") (pinfunction "VSS_J9") (pintype "passive"))
      (node (ref "U16") (pin "K10") (pinfunction "VSS_K10") (pintype "passive"))
      (node (ref "U16") (pin "K6") (pinfunction "VSS_K6") (pintype "passive"))
      (node (ref "U16") (pin "K7") (pinfunction "VSS_K7") (pintype "passive"))
      (node (ref "U16") (pin "K8") (pinfunction "VSS_K8") (pintype "passive"))
      (node (ref "U16") (pin "K9") (pinfunction "VSS_K9") (pintype "passive"))
      (node (ref "U16") (pin "M1") (pinfunction "VSSA_M1") (pintype "passive"))
      (node (ref "U16") (pin "M8") (pinfunction "VSS_M8") (pintype "passive"))
      (node (ref "U16") (pin "M9") (pinfunction "VSS_M9") (pintype "passive"))
      (node (ref "U16") (pin "N1") (pinfunction "VREF-_N1") (pintype "passive"))
      (node (ref "U24") (pin "2") (pinfunction "GND_2") (pintype "passive"))
      (node (ref "U28") (pin "2") (pinfunction "GND_2") (pintype "passive"))
    )
    (net (code "11") (name "Net-(D10-K)") (class "Default")
      (node (ref "C122") (pin "2") (pinfunction "2_2") (pintype "passive"))
      (node (ref "C126") (pin "1") (pinfunction "1_1") (pintype "passive"))
      (node (ref "D10") (pin "2") (pinfunction "K_2") (pintype "passive"))
      (node (ref "D11") (pin "2") (pinfunction "K_2") (pintype "passive"))
      (node (ref "D12") (pin "2") (pinfunction "K_2") (pintype "passive"))
      (node (ref "D13") (pin "2") (pinfunction "K_2") (pintype "passive"))
      (node (ref "D9") (pin "2") (pinfunction "K_2") (pintype "passive"))
      (node (ref "U14") (pin "1") (pinfunction "Vin_1") (pintype "passive"))
      (node (ref "U14") (pin "3") (pinfunction "CE_3") (pintype "passive"))
    )
    (net (code "12") (name "Net-(LD3-Pad1)") (class "Default")
      (node (ref "LD3") (pin "1") (pintype "passive"))
      (node (ref "R215") (pin "1") (pinfunction "1_1") (pintype "passive"))
    )
    (net (code "13") (name "Net-(LD4-Pad1)") (class "Default")
      (node (ref "LD4") (pin "1") (pintype "passive"))
      (node (ref "R216") (pin "2") (pinfunction "2_2") (pintype "passive"))
    )
    (net (code "14") (name "Net-(U14-BYPASS)") (class "Default")
      (node (ref "C124") (pin "2") (pinfunction "2_2") (pintype "passive"))
      (node (ref "U14") (pin "4") (pinfunction "BYPASS_4") (pintype "passive"))
    )
    (net (code "15") (name "Net-(U16B-BYPASS-REG)") (class "Default")
      (node (ref "R196") (pin "2") (pinfunction "2_2") (pintype "passive"))
      (node (ref "U16") (pin "L4") (pinfunction "BYPASS-REG_L4") (pintype "passive"))
    )
    (net (code "16") (name "Net-(U16B-VCAP1)") (class "Default")
      (node (ref "C108") (pin "2") (pinfunction "2_2") (pintype "passive"))
      (node (ref "U16") (pin "M10") (pinfunction "VCAP1_M10") (pintype "passive"))
    )
    (net (code "17") (name "Net-(U16B-VCAP2)") (class "Default")
      (node (ref "C107") (pin "2") (pinfunction "2_2") (pintype "passive"))
      (node (ref "U16") (pin "F13") (pinfunction "VCAP2_F13") (pintype "passive"))
    )
    (net (code "18") (name "Net-(U24-~{FAULT})") (class "Default")
      (node (ref "LD3") (pin "2") (pintype "passive"))
      (node (ref "R218") (pin "1") (pinfunction "1_1") (pintype "passive"))
      (node (ref "U24") (pin "3") (pinfunction "~{FAULT}_3") (pintype "passive"))
    )
    (net (code "19") (name "VBUS_FS2") (class "Default")
      (node (ref "D13") (pin "1") (pinfunction "A_1") (pintype "passive"))
      (node (ref "JP8") (pin "5") (pinfunction "5_5") (pintype "passive"))
    )
    (net (code "20") (name "unconnected-(CN15-DM-Pad2)") (class "Default")
      (node (ref "CN15") (pin "2") (pinfunction "DM_2") (pintype "passive+no_connect"))
    )
    (net (code "21") (name "unconnected-(CN15-DP-Pad3)") (class "Default")
      (node (ref "CN15") (pin "3") (pinfunction "DP_3") (pintype "passive+no_connect"))
    )
    (net (code "22") (name "unconnected-(CN15-ID-Pad4)") (class "Default")
      (node (ref "CN15") (pin "4") (pinfunction "ID_4") (pintype "passive+no_connect"))
    )
  )
)
